# a_pub_sub_upper_system.net
KiCad netlist of a schematic drawn in EAGLE
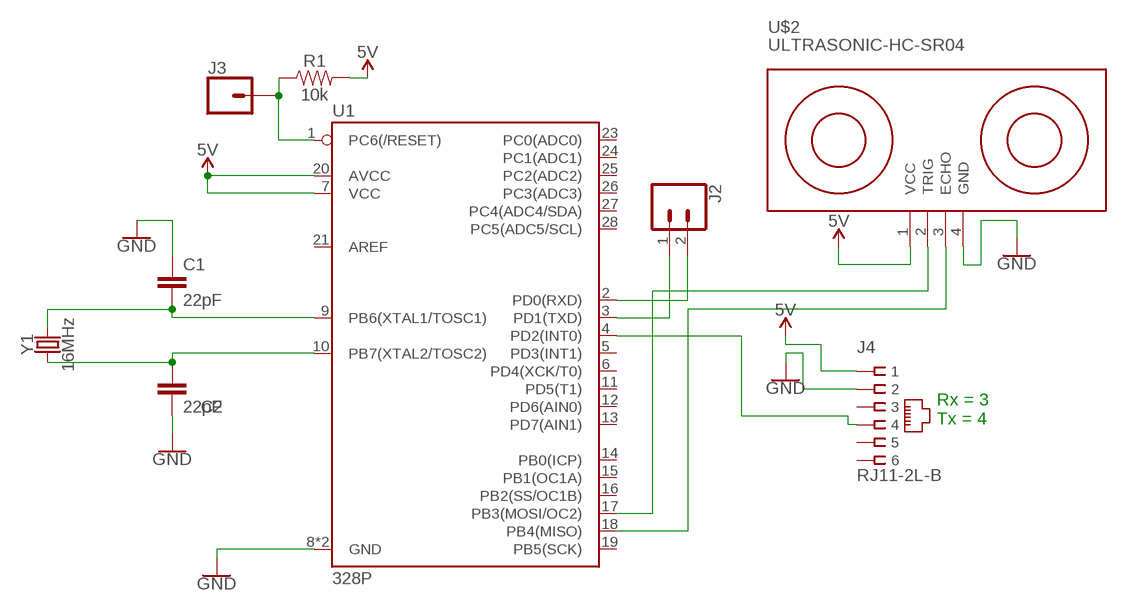
[diagram p0: schematic, sheet 1]

(export (version "E")
  (design (tool "Eeschema 10.0.6"))
  (components
    (comp (ref "C1")
      (value "22pF")
      (footprint "eagle-import:CAP-PTH-2.54")
      (libsource (lib "eagle-import") (part "22PF-PTH-2.54MM-200V-5%"))
    )
    (comp (ref "C2")
      (value "22pF")
      (footprint "eagle-import:CAP-PTH-2.54")
      (libsource (lib "eagle-import") (part "22PF-PTH-2.54MM-200V-5%"))
    )
    (comp (ref "J2")
      (value "CONN_025MM")
      (footprint "eagle-import:SCREWTERMINAL-5MM-2")
      (libsource (lib "eagle-import") (part "CONN_025MM"))
    )
    (comp (ref "J3")
      (value "CONN_01")
      (footprint "eagle-import:1X01")
      (libsource (lib "eagle-import") (part "CONN_01"))
    )
    (comp (ref "J4")
      (value "RJ11-2L-B")
      (footprint "eagle-import:RJ11-NO_SHIELD")
      (fields (field (name "MF") "TYCO ELECTRONICS"))
      (libsource (lib "eagle-import") (part "RJ11-2L-B"))
    )
    (comp (ref "R1")
      (value "10k")
      (footprint "eagle-import:AXIAL-0.3")
      (libsource (lib "eagle-import") (part "10KOHM-HORIZ-1/4W-1%"))
    )
    (comp (ref "U$2")
      (value "ULTRASONIC-HC-SR04")
      (footprint "eagle-import:ULTRASONIC-HC-SR04")
      (libsource (lib "eagle-import") (part "ULTRASONIC-HC-SR04"))
    )
    (comp (ref "U1")
      (value "328P")
      (footprint "eagle-import:DIP28")
      (libsource (lib "eagle-import") (part "ATMEGA328P_PDIP"))
    )
    (comp (ref "Y1")
      (value "16MHz")
      (footprint "eagle-import:HC49US")
      (libsource (lib "eagle-import") (part "CRYSTAL-16MHZPTH-HC49US"))
    )
  )
  (nets
    (net (code "1") (name "5V") (class "Default")
      (node (ref "J4") (pin "1") (pinfunction "1_1") (pintype "passive"))
      (node (ref "R1") (pin "P$2") (pinfunction "2_P$2") (pintype "passive"))
      (node (ref "U$2") (pin "1") (pinfunction "VCC_1") (pintype "power_in"))
      (node (ref "U1") (pin "20") (pinfunction "AVCC_20") (pintype "bidirectional"))
      (node (ref "U1") (pin "7") (pinfunction "VCC_7") (pintype "bidirectional"))
    )
    (net (code "2") (name "GND") (class "Default")
      (node (ref "C1") (pin "1") (pinfunction "1_1") (pintype "passive"))
      (node (ref "C2") (pin "2") (pinfunction "2_2") (pintype "passive"))
      (node (ref "J4") (pin "2") (pinfunction "2_2") (pintype "passive"))
      (node (ref "U$2") (pin "4") (pinfunction "GND_4") (pintype "power_in"))
      (node (ref "U1") (pin "22") (pinfunction "GND_22") (pintype "bidirectional"))
      (node (ref "U1") (pin "8") (pinfunction "GND_8") (pintype "bidirectional"))
    )
    (net (code "3") (name "Net-(R1-1)") (class "Default")
      (node (ref "J3") (pin "1") (pinfunction "1_1") (pintype "passive"))
      (node (ref "R1") (pin "P$1") (pinfunction "1_P$1") (pintype "passive"))
      (node (ref "U1") (pin "1") (pinfunction "PC6(/RESET)_1") (pintype "bidirectional"))
    )
    (net (code "4") (name "Net-(U$2-ECHO)") (class "Default")
      (node (ref "U$2") (pin "3") (pinfunction "ECHO_3") (pintype "output"))
      (node (ref "U1") (pin "18") (pinfunction "PB4(MISO)_18") (pintype "bidirectional"))
    )
    (net (code "5") (name "Net-(U$2-TRIG)") (class "Default")
      (node (ref "U$2") (pin "2") (pinfunction "TRIG_2") (pintype "input"))
      (node (ref "U1") (pin "17") (pinfunction "PB3(MOSI/OC2)_17") (pintype "bidirectional"))
    )
    (net (code "6") (name "Net-(U1-PB6(XTAL1{slash}TOSC1))") (class "Default")
      (node (ref "C1") (pin "2") (pinfunction "2_2") (pintype "passive"))
      (node (ref "U1") (pin "9") (pinfunction "PB6(XTAL1/TOSC1)_9") (pintype "bidirectional"))
      (node (ref "Y1") (pin "2") (pinfunction "2_2") (pintype "passive"))
    )
    (net (code "7") (name "Net-(U1-PB7(XTAL2{slash}TOSC2))") (class "Default")
      (node (ref "C2") (pin "1") (pinfunction "1_1") (pintype "passive"))
      (node (ref "U1") (pin "10") (pinfunction "PB7(XTAL2/TOSC2)_10") (pintype "bidirectional"))
      (node (ref "Y1") (pin "1") (pinfunction "1_1") (pintype "passive"))
    )
    (net (code "8") (name "Net-(U1-PD0(RXD))") (class "Default")
      (node (ref "J2") (pin "2") (pinfunction "2_2") (pintype "passive"))
      (node (ref "U1") (pin "2") (pinfunction "PD0(RXD)_2") (pintype "bidirectional"))
    )
    (net (code "9") (name "Net-(U1-PD1(TXD))") (class "Default")
      (node (ref "J2") (pin "1") (pinfunction "1_1") (pintype "passive"))
      (node (ref "U1") (pin "3") (pinfunction "PD1(TXD)_3") (pintype "bidirectional"))
    )
    (net (code "10") (name "Net-(U1-PD2(INT0))") (class "Default")
      (node (ref "J4") (pin "4") (pinfunction "4_4") (pintype "passive"))
      (node (ref "U1") (pin "4") (pinfunction "PD2(INT0)_4") (pintype "bidirectional"))
    )
    (net (code "11") (name "unconnected-(J4-Pad3)") (class "Default")
      (node (ref "J4") (pin "3") (pinfunction "3_3") (pintype "passive"))
    )
    (net (code "12") (name "unconnected-(J4-Pad5)") (class "Default")
      (node (ref "J4") (pin "5") (pinfunction "5_5") (pintype "passive"))
    )
    (net (code "13") (name "unconnected-(J4-Pad6)") (class "Default")
      (node (ref "J4") (pin "6") (pinfunction "6_6") (pintype "passive"))
    )
    (net (code "14") (name "unconnected-(U1-AREF-Pad21)") (class "Default")
      (node (ref "U1") (pin "21") (pinfunction "AREF_21") (pintype "bidirectional"))
    )
    (net (code "15") (name "unconnected-(U1-PB0(ICP)-Pad14)") (class "Default")
      (node (ref "U1") (pin "14") (pinfunction "PB0(ICP)_14") (pintype "bidirectional"))
    )
    (net (code "16") (name "unconnected-(U1-PB1(OC1A)-Pad15)") (class "Default")
      (node (ref "U1") (pin "15") (pinfunction "PB1(OC1A)_15") (pintype "bidirectional"))
    )
    (net (code "17") (name "unconnected-(U1-PB2(SS{slash}OC1B)-Pad16)") (class "Default")
      (node (ref "U1") (pin "16") (pinfunction "PB2(SS/OC1B)_16") (pintype "bidirectional"))
    )
    (net (code "18") (name "unconnected-(U1-PB5(SCK)-Pad19)") (class "Default")
      (node (ref "U1") (pin "19") (pinfunction "PB5(SCK)_19") (pintype "bidirectional"))
    )
    (net (code "19") (name "unconnected-(U1-PC0(ADC0)-Pad23)") (class "Default")
      (node (ref "U1") (pin "23") (pinfunction "PC0(ADC0)_23") (pintype "bidirectional"))
    )
    (net (code "20") (name "unconnected-(U1-PC1(ADC1)-Pad24)") (class "Default")
      (node (ref "U1") (pin "24") (pinfunction "PC1(ADC1)_24") (pintype "bidirectional"))
    )
    (net (code "21") (name "unconnected-(U1-PC2(ADC2)-Pad25)") (class "Default")
      (node (ref "U1") (pin "25") (pinfunction "PC2(ADC2)_25") (pintype "bidirectional"))
    )
    (net (code "22") (name "unconnected-(U1-PC3(ADC3)-Pad26)") (class "Default")
      (node (ref "U1") (pin "26") (pinfunction "PC3(ADC3)_26") (pintype "bidirectional"))
    )
    (net (code "23") (name "unconnected-(U1-PC4(ADC4{slash}SDA)-Pad27)") (class "Default")
      (node (ref "U1") (pin "27") (pinfunction "PC4(ADC4/SDA)_27") (pintype "bidirectional"))
    )
    (net (code "24") (name "unconnected-(U1-PC5(ADC5{slash}SCL)-Pad28)") (class "Default")
      (node (ref "U1") (pin "28") (pinfunction "PC5(ADC5/SCL)_28") (pintype "bidirectional"))
    )
    (net (code "25") (name "unconnected-(U1-PD3(INT1)-Pad5)") (class "Default")
      (node (ref "U1") (pin "5") (pinfunction "PD3(INT1)_5") (pintype "bidirectional"))
    )
    (net (code "26") (name "unconnected-(U1-PD4(XCK{slash}T0)-Pad6)") (class "Default")
      (node (ref "U1") (pin "6") (pinfunction "PD4(XCK/T0)_6") (pintype "bidirectional"))
    )
    (net (code "27") (name "unconnected-(U1-PD5(T1)-Pad11)") (class "Default")
      (node (ref "U1") (pin "11") (pinfunction "PD5(T1)_11") (pintype "bidirectional"))
    )
    (net (code "28") (name "unconnected-(U1-PD6(AIN0)-Pad12)") (class "Default")
      (node (ref "U1") (pin "12") (pinfunction "PD6(AIN0)_12") (pintype "bidirectional"))
    )
    (net (code "29") (name "unconnected-(U1-PD7(AIN1)-Pad13)") (class "Default")
      (node (ref "U1") (pin "13") (pinfunction "PD7(AIN1)_13") (pintype "bidirectional"))
    )
  )
)
